# DIGITAL_IO.net
KiCad netlist of a schematic drawn in Altium Designer
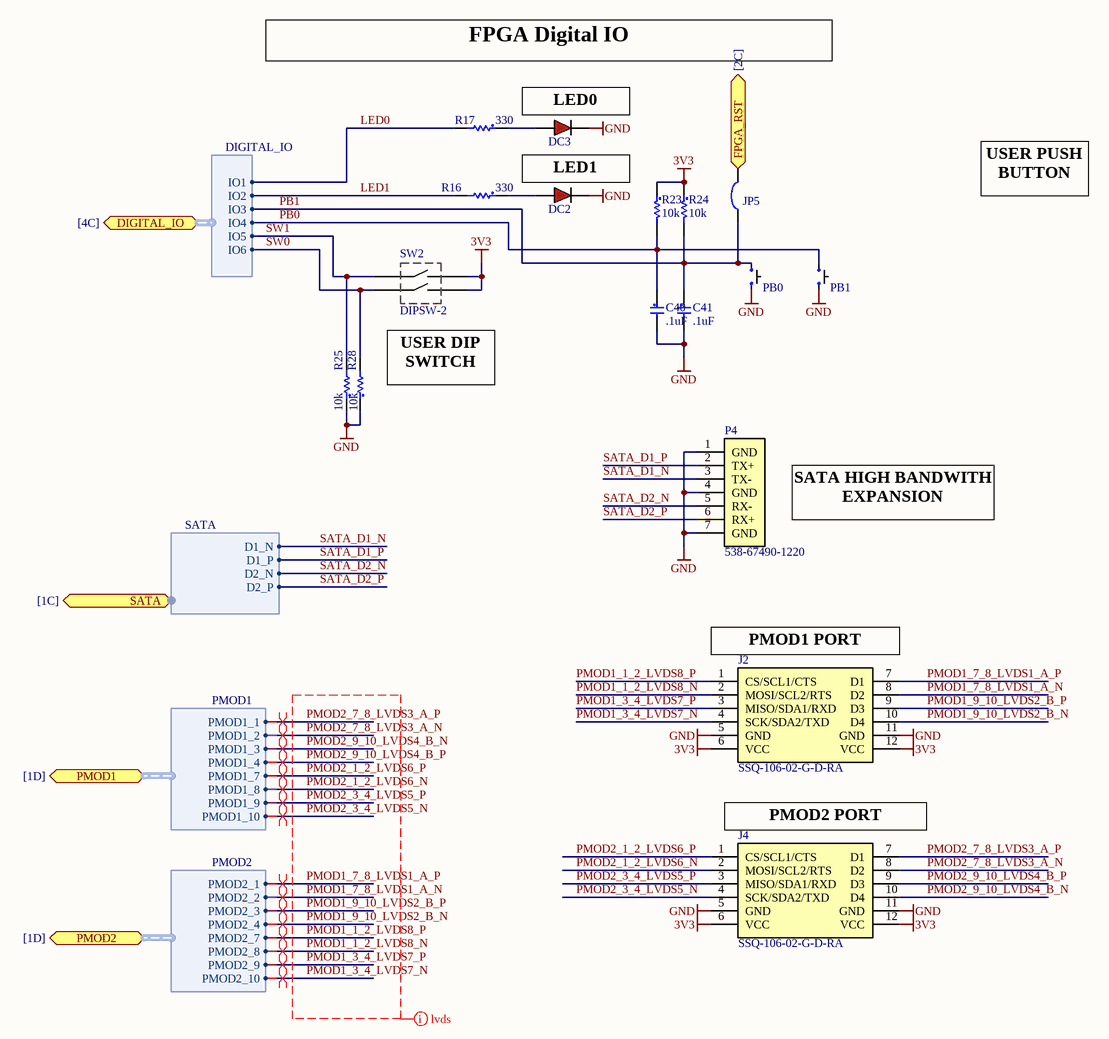
[diagram p0: DIGITAL_IO.SchDoc]

(export (version "E")
  (design (tool "Eeschema 10.0.6"))
  (components
    (comp (ref "C40")
      (value ".1uF")
      (footprint "c0603")
      (description "CAP CER 0.1UF 25V Y5V 0603")
      (fields
        (field (name "MANUFACTURER") "Samsung Electro-Mechanics America, Inc")
        (field (name "MANUFACTURER PART NUMBER") "CL10F104ZA8NNNC")
      )
      (libsource (lib "mCapacitors") (part "C0603 - CL10F104ZA8NNNC"))
    )
    (comp (ref "C41")
      (value ".1uF")
      (footprint "c0603")
      (description "CAP CER 0.1UF 25V Y5V 0603")
      (fields
        (field (name "MANUFACTURER") "Samsung Electro-Mechanics America, Inc")
        (field (name "MANUFACTURER PART NUMBER") "CL10F104ZA8NNNC")
      )
      (libsource (lib "mCapacitors") (part "C0603 - CL10F104ZA8NNNC"))
    )
    (comp (ref "DC2")
      (value "598-8010-107F")
      (footprint "LED_0603 - RED")
      (description "LED ALINGAP RED CLEAR 0603 SMD")
      (fields (field (name "MANUFACTURER") "Dialight"))
      (libsource (lib "mDiode") (part "LED0603 - 598-8010-107F"))
    )
    (comp (ref "DC3")
      (value "598-8010-107F")
      (footprint "LED_0603 - RED")
      (description "LED ALINGAP RED CLEAR 0603 SMD")
      (fields (field (name "MANUFACTURER") "Dialight"))
      (libsource (lib "mDiode") (part "LED0603 - 598-8010-107F"))
    )
    (comp (ref "J2")
      (value "SSQ-106-02-G-D-RA")
      (footprint "PMOD HEADER - SSQ-106-02-G-D-RA")
      (description "SAMTEC - SSQ-106-02-G-D-RA-005 - 2MM SOCKET STRIPS")
      (fields (field (name "MANUFACTURER") "SAMTEC"))
      (libsource (lib "mConnector") (part "P-MOD - SSQ-106-02-G-D-RA"))
    )
    (comp (ref "J4")
      (value "SSQ-106-02-G-D-RA")
      (footprint "PMOD HEADER - SSQ-106-02-G-D-RA")
      (description "SAMTEC - SSQ-106-02-G-D-RA-005 - 2MM SOCKET STRIPS")
      (fields (field (name "MANUFACTURER") "SAMTEC"))
      (libsource (lib "mConnector") (part "P-MOD - SSQ-106-02-G-D-RA"))
    )
    (comp (ref "JP5")
      (value "Solder Jumper")
      (footprint "SOLDER_JUMPER")
      (description "Solder/Configuration Jumper")
      (fields (field (name "MANUFACTURER") "n/a"))
      (libsource (lib "mConnector") (part "Solder Jumper"))
    )
    (comp (ref "P4")
      (value "SATA - 67490-1220")
      (footprint "SATA - 67490-3220")
      (description "SATA Data - 67490-1220")
      (fields
        (field (name "MANUFACTURER") "Molex")
        (field (name "MANUFACTURER PART NUMBER") "67490-1220")
        (field (name "SUPPLIER PART NUMBER 1") "538-67490-1220")
      )
      (libsource (lib "mConnector") (part "SATA - 67490-1220"))
    )
    (comp (ref "PB0")
      (value "~")
      (footprint "mElectroMechanical:FSM4JSMA")
      (description "SWITCH TACTILE SPST-NO 0.05A 12V")
      (fields
        (field (name "MANUFACTURER") "TE Connectivity")
        (field (name "MANUFACTURER PART NUMBER") "FSM4JSMA")
      )
      (libsource (lib "mElectroMechanical") (part "FSM4JSMATR"))
    )
    (comp (ref "PB1")
      (value "~")
      (footprint "mElectroMechanical:FSM4JSMA")
      (description "SWITCH TACTILE SPST-NO 0.05A 12V")
      (fields
        (field (name "MANUFACTURER") "TE Connectivity")
        (field (name "MANUFACTURER PART NUMBER") "FSM4JSMA")
      )
      (libsource (lib "mElectroMechanical") (part "FSM4JSMATR"))
    )
    (comp (ref "R16")
      (value "330")
      (footprint "R0603")
      (description "Thick Film Resistors - SMD 0603 330ohms 5% Tol")
      (fields
        (field (name "MANUFACTURER") "Panasonic")
        (field (name "MANUFACTURER PART NUMBER") "ERJ-3GEYJ331V")
      )
      (libsource (lib "mResistors") (part "R0603 - ERJ-3GEYJ331V"))
    )
    (comp (ref "R17")
      (value "330")
      (footprint "R0603")
      (description "Thick Film Resistors - SMD 0603 330ohms 5% Tol")
      (fields
        (field (name "MANUFACTURER") "Panasonic")
        (field (name "MANUFACTURER PART NUMBER") "ERJ-3GEYJ331V")
      )
      (libsource (lib "mResistors") (part "R0603 - ERJ-3GEYJ331V"))
    )
    (comp (ref "R23")
      (value "10k")
      (footprint "mRCL:R0603")
      (description "10k Thick Film Resistors - SMD 1/10watt 10Kohms 1%")
      (fields
        (field (name "MANUFACTURER") "Vishay Dale")
        (field (name "MANUFACTURER PART NUMBER") "CRCW060310K0FKEA")
      )
      (libsource (lib "mResistors") (part "R0603 - CRCW060310K0FKEA"))
    )
    (comp (ref "R24")
      (value "10k")
      (footprint "mRCL:R0603")
      (description "10k Thick Film Resistors - SMD 1/10watt 10Kohms 1%")
      (fields
        (field (name "MANUFACTURER") "Vishay Dale")
        (field (name "MANUFACTURER PART NUMBER") "CRCW060310K0FKEA")
      )
      (libsource (lib "mResistors") (part "R0603 - CRCW060310K0FKEA"))
    )
    (comp (ref "R25")
      (value "10k")
      (footprint "mRCL:R0603")
      (description "10k Thick Film Resistors - SMD 1/10watt 10Kohms 1%")
      (fields
        (field (name "MANUFACTURER") "Vishay Dale")
        (field (name "MANUFACTURER PART NUMBER") "CRCW060310K0FKEA")
      )
      (libsource (lib "") (part "R0603 - CRCW060310K0FKEA_1"))
    )
    (comp (ref "R28")
      (value "10k")
      (footprint "mRCL:R0603")
      (description "10k Thick Film Resistors - SMD 1/10watt 10Kohms 1%")
      (fields
        (field (name "MANUFACTURER") "Vishay Dale")
        (field (name "MANUFACTURER PART NUMBER") "CRCW060310K0FKEA")
      )
      (libsource (lib "") (part "R0603 - CRCW060310K0FKEA_1"))
    )
    (comp (ref "SW2")
      (value "DIPSW-2")
      (footprint "DIPSW - 219-2MST")
      (description "DIP Switches / SIP Switches SPST 2 switch sections")
      (fields
        (field (name "MANUFACTURER") "CTS Electronic Components")
        (field (name "MANUFACTURER PART NUMBER") "219-2MST")
      )
      (libsource (lib "mElectroMechanical") (part "DIPSW - 219-2MST"))
    )
  )
  (nets
    (net (code "5") (name "/FPGA_RST") (class "Default")
      (node (ref "JP5") (pin "2") (pinfunction "2_2") (pintype "passive"))
    )
    (net (code "6") (name "/LED0") (class "Default")
      (node (ref "R17") (pin "2") (pinfunction "2_2") (pintype "passive"))
    )
    (net (code "7") (name "/LED1") (class "Default")
      (node (ref "R16") (pin "2") (pinfunction "2_2") (pintype "passive"))
    )
    (net (code "8") (name "/PB0") (class "Default")
      (node (ref "C40") (pin "1") (pinfunction "1_1") (pintype "passive"))
      (node (ref "PB1") (pin "B") (pinfunction "B_B") (pintype "passive"))
      (node (ref "R23") (pin "2") (pinfunction "2_2") (pintype "passive"))
    )
    (net (code "9") (name "/PB1") (class "Default")
      (node (ref "C41") (pin "1") (pinfunction "1_1") (pintype "passive"))
      (node (ref "JP5") (pin "1") (pinfunction "1_1") (pintype "passive"))
      (node (ref "PB0") (pin "B") (pinfunction "B_B") (pintype "passive"))
      (node (ref "R24") (pin "2") (pinfunction "2_2") (pintype "passive"))
    )
    (net (code "10") (name "/PMOD1_1_2_LVDS8_N") (class "Default")
      (node (ref "J2") (pin "2") (pinfunction "MOSI/SCL2/RTS_2") (pintype "power_in"))
    )
    (net (code "11") (name "/PMOD1_1_2_LVDS8_P") (class "Default")
      (node (ref "J2") (pin "1") (pinfunction "CS/SCL1/CTS_1") (pintype "power_in"))
    )
    (net (code "12") (name "/PMOD1_3_4_LVDS7_N") (class "Default")
      (node (ref "J2") (pin "4") (pinfunction "SCK/SDA2/TXD_4") (pintype "power_in"))
    )
    (net (code "13") (name "/PMOD1_3_4_LVDS7_P") (class "Default")
      (node (ref "J2") (pin "3") (pinfunction "MISO/SDA1/RXD_3") (pintype "power_in"))
    )
    (net (code "14") (name "/PMOD1_7_8_LVDS1_A_N") (class "Default")
      (node (ref "J2") (pin "8") (pinfunction "D2_8") (pintype "power_in"))
    )
    (net (code "15") (name "/PMOD1_7_8_LVDS1_A_P") (class "Default")
      (node (ref "J2") (pin "7") (pinfunction "D1_7") (pintype "power_in"))
    )
    (net (code "16") (name "/PMOD1_9_10_LVDS2_B_N") (class "Default")
      (node (ref "J2") (pin "10") (pinfunction "D4_10") (pintype "power_in"))
    )
    (net (code "17") (name "/PMOD1_9_10_LVDS2_B_P") (class "Default")
      (node (ref "J2") (pin "9") (pinfunction "D3_9") (pintype "power_in"))
    )
    (net (code "18") (name "/PMOD2_1_2_LVDS6_N") (class "Default")
      (node (ref "J4") (pin "2") (pinfunction "MOSI/SCL2/RTS_2") (pintype "power_in"))
    )
    (net (code "19") (name "/PMOD2_1_2_LVDS6_P") (class "Default")
      (node (ref "J4") (pin "1") (pinfunction "CS/SCL1/CTS_1") (pintype "power_in"))
    )
    (net (code "20") (name "/PMOD2_3_4_LVDS5_N") (class "Default")
      (node (ref "J4") (pin "4") (pinfunction "SCK/SDA2/TXD_4") (pintype "power_in"))
    )
    (net (code "21") (name "/PMOD2_3_4_LVDS5_P") (class "Default")
      (node (ref "J4") (pin "3") (pinfunction "MISO/SDA1/RXD_3") (pintype "power_in"))
    )
    (net (code "22") (name "/PMOD2_7_8_LVDS3_A_N") (class "Default")
      (node (ref "J4") (pin "8") (pinfunction "D2_8") (pintype "power_in"))
    )
    (net (code "23") (name "/PMOD2_7_8_LVDS3_A_P") (class "Default")
      (node (ref "J4") (pin "7") (pinfunction "D1_7") (pintype "power_in"))
    )
    (net (code "24") (name "/PMOD2_9_10_LVDS4_B_N") (class "Default")
      (node (ref "J4") (pin "10") (pinfunction "D4_10") (pintype "power_in"))
    )
    (net (code "25") (name "/PMOD2_9_10_LVDS4_B_P") (class "Default")
      (node (ref "J4") (pin "9") (pinfunction "D3_9") (pintype "power_in"))
    )
    (net (code "26") (name "/SATA_D1_N") (class "Default")
      (node (ref "P4") (pin "3") (pinfunction "TX-_3") (pintype "passive"))
    )
    (net (code "27") (name "/SATA_D1_P") (class "Default")
      (node (ref "P4") (pin "2") (pinfunction "TX+_2") (pintype "passive"))
    )
    (net (code "28") (name "/SATA_D2_N") (class "Default")
      (node (ref "P4") (pin "5") (pinfunction "RX-_5") (pintype "passive"))
    )
    (net (code "29") (name "/SATA_D2_P") (class "Default")
      (node (ref "P4") (pin "6") (pinfunction "RX+_6") (pintype "passive"))
    )
    (net (code "30") (name "/SW0") (class "Default")
      (node (ref "R28") (pin "2") (pinfunction "2_2") (pintype "passive"))
      (node (ref "SW2") (pin "A2") (pinfunction "A2_A2") (pintype "passive"))
    )
    (net (code "31") (name "/SW1") (class "Default")
      (node (ref "R25") (pin "2") (pinfunction "2_2") (pintype "passive"))
      (node (ref "SW2") (pin "A1") (pinfunction "A1_A1") (pintype "passive"))
    )
    (net (code "36") (name "3V3") (class "Default")
      (node (ref "J2") (pin "12") (pinfunction "VCC_12") (pintype "power_in"))
      (node (ref "J2") (pin "6") (pinfunction "VCC_6") (pintype "power_in"))
      (node (ref "J4") (pin "12") (pinfunction "VCC_12") (pintype "power_in"))
      (node (ref "J4") (pin "6") (pinfunction "VCC_6") (pintype "power_in"))
      (node (ref "R23") (pin "1") (pinfunction "1_1") (pintype "passive"))
      (node (ref "R24") (pin "1") (pinfunction "1_1") (pintype "passive"))
      (node (ref "SW2") (pin "B1") (pinfunction "B1_B1") (pintype "passive"))
      (node (ref "SW2") (pin "B2") (pinfunction "B2_B2") (pintype "passive"))
    )
    (net (code "37") (name "GND") (class "Default")
      (node (ref "C40") (pin "2") (pinfunction "2_2") (pintype "passive"))
      (node (ref "C41") (pin "2") (pinfunction "2_2") (pintype "passive"))
      (node (ref "DC2") (pin "C") (pinfunction "C_C") (pintype "passive"))
      (node (ref "DC3") (pin "C") (pinfunction "C_C") (pintype "passive"))
      (node (ref "J2") (pin "11") (pinfunction "GND_11") (pintype "power_in"))
      (node (ref "J2") (pin "5") (pinfunction "GND_5") (pintype "power_in"))
      (node (ref "J4") (pin "11") (pinfunction "GND_11") (pintype "power_in"))
      (node (ref "J4") (pin "5") (pinfunction "GND_5") (pintype "power_in"))
      (node (ref "P4") (pin "1") (pinfunction "GND_1") (pintype "passive"))
      (node (ref "P4") (pin "4") (pinfunction "GND_4") (pintype "passive"))
      (node (ref "P4") (pin "7") (pinfunction "GND_7") (pintype "passive"))
      (node (ref "PB0") (pin "A") (pinfunction "A_A") (pintype "passive"))
      (node (ref "PB1") (pin "A") (pinfunction "A_A") (pintype "passive"))
      (node (ref "R25") (pin "1") (pinfunction "1_1") (pintype "passive"))
      (node (ref "R28") (pin "1") (pinfunction "1_1") (pintype "passive"))
    )
    (net (code "38") (name "Net-(DC2-PadA)") (class "Default")
      (node (ref "DC2") (pin "A") (pinfunction "A_A") (pintype "passive"))
      (node (ref "R16") (pin "1") (pinfunction "1_1") (pintype "passive"))
    )
    (net (code "39") (name "Net-(DC3-PadA)") (class "Default")
      (node (ref "DC3") (pin "A") (pinfunction "A_A") (pintype "passive"))
      (node (ref "R17") (pin "1") (pinfunction "1_1") (pintype "passive"))
    )
  )
)
